# Encoder.net
KiCad netlist of a schematic drawn in Altium Designer
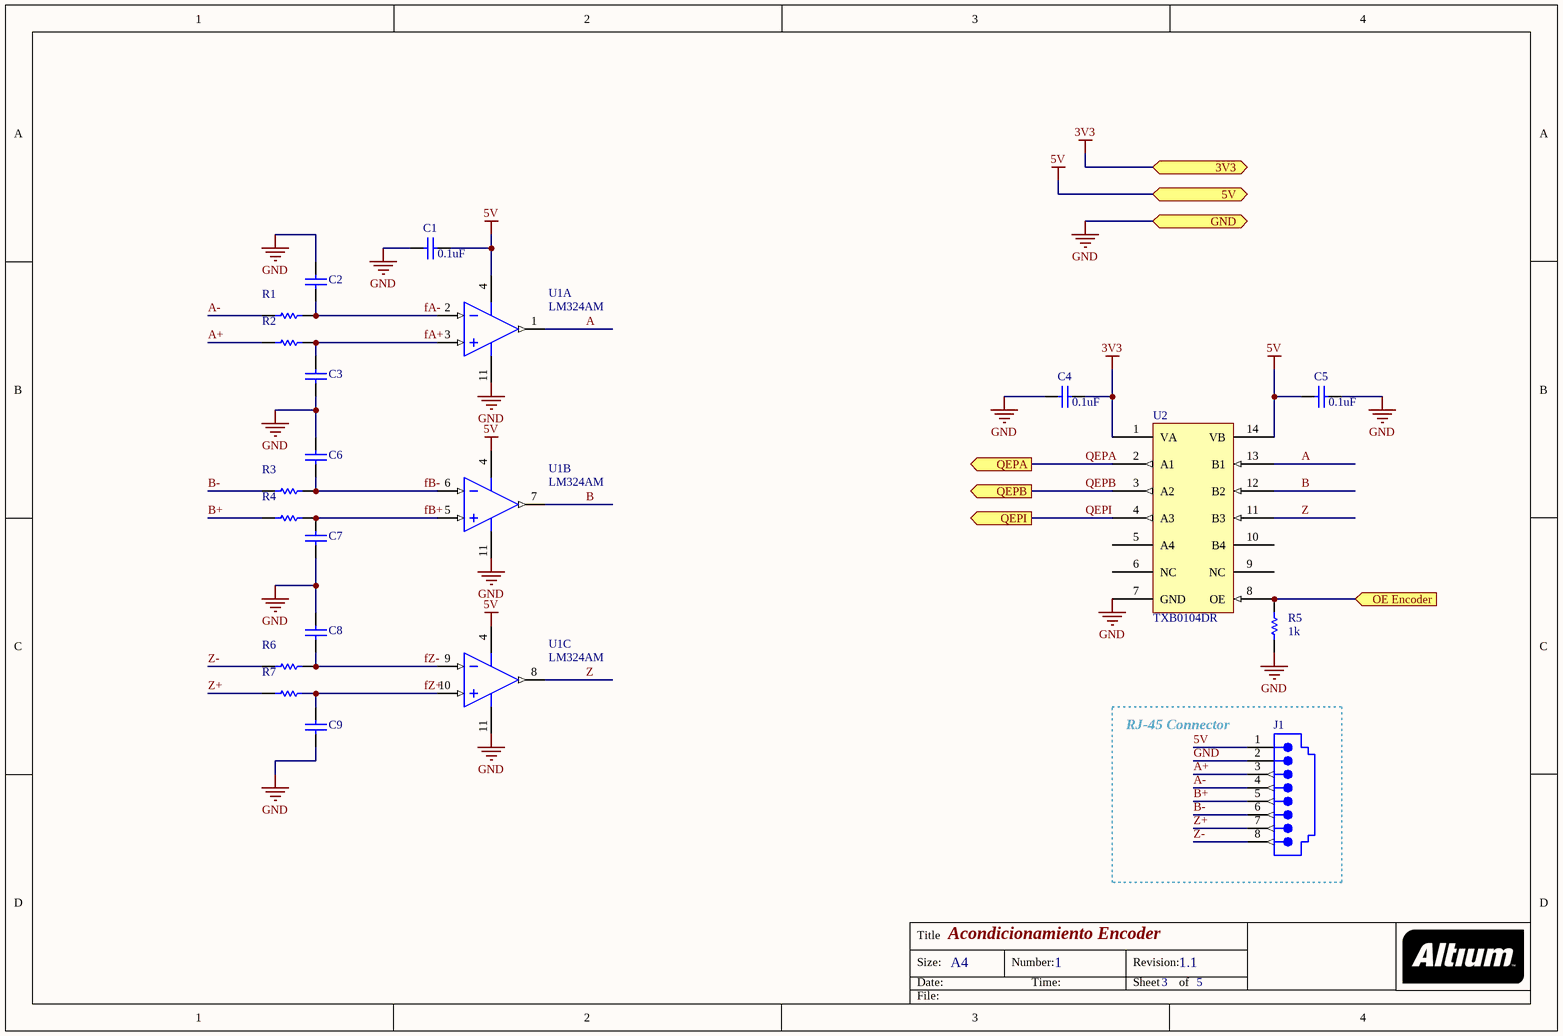
[diagram p0: Encoder.SchDoc]

(export (version "E")
  (design (tool "Eeschema 10.0.6"))
  (components
    (comp (ref "C1")
      (value "0.1uF")
      (footprint "C 1206")
      (description "Capacitor")
      (fields (field (name "Comment") "C0.1u") (field (name ".CREATOR") "SR"))
      (libsource (lib "CDR_SCH") (part "C"))
    )
    (comp (ref "C2")
      (value "C?")
      (footprint "C 1206")
      (description "Capacitor")
      (fields (field (name ".CREATOR") "SR"))
      (libsource (lib "CDR_SCH") (part "C"))
    )
    (comp (ref "C3")
      (value "C?")
      (footprint "C 1206")
      (description "Capacitor")
      (fields (field (name ".CREATOR") "SR"))
      (libsource (lib "CDR_SCH") (part "C"))
    )
    (comp (ref "C4")
      (value "0.1uF")
      (footprint "C 1206")
      (description "Capacitor")
      (fields (field (name "Comment") "C0.1u") (field (name ".CREATOR") "SR"))
      (libsource (lib "CDR_SCH") (part "C"))
    )
    (comp (ref "C5")
      (value "0.1uF")
      (footprint "C 1206")
      (description "Capacitor")
      (fields (field (name "Comment") "C0.1u") (field (name ".CREATOR") "SR"))
      (libsource (lib "CDR_SCH") (part "C"))
    )
    (comp (ref "C6")
      (value "C?")
      (footprint "C 1206")
      (description "Capacitor")
      (fields (field (name ".CREATOR") "SR"))
      (libsource (lib "CDR_SCH") (part "C"))
    )
    (comp (ref "C7")
      (value "C?")
      (footprint "C 1206")
      (description "Capacitor")
      (fields (field (name ".CREATOR") "SR"))
      (libsource (lib "CDR_SCH") (part "C"))
    )
    (comp (ref "C8")
      (value "C?")
      (footprint "C 1206")
      (description "Capacitor")
      (fields (field (name ".CREATOR") "SR"))
      (libsource (lib "CDR_SCH") (part "C"))
    )
    (comp (ref "C9")
      (value "C?")
      (footprint "C 1206")
      (description "Capacitor")
      (fields (field (name ".CREATOR") "SR"))
      (libsource (lib "CDR_SCH") (part "C"))
    )
    (comp (ref "J1")
      (value "RJ-45 connector")
      (footprint "15-43-6588")
      (description "RJ-45 connector, 8-pins, ethernet")
      (fields (field (name "PUBLISHER") "Altium Limited"))
      (libsource (lib "Molex Modular Jack Right Angle") (part "15-43-6588"))
    )
    (comp (ref "R1")
      (value "R?")
      (footprint "R 1206")
      (description "Resistencia")
      (fields (field (name ".CREATOR") "SR"))
      (libsource (lib "CDR_SCH") (part "R"))
    )
    (comp (ref "R2")
      (value "R?")
      (footprint "R 1206")
      (description "Resistencia")
      (fields (field (name ".CREATOR") "SR"))
      (libsource (lib "CDR_SCH") (part "R"))
    )
    (comp (ref "R3")
      (value "R?")
      (footprint "R 1206")
      (description "Resistencia")
      (fields (field (name ".CREATOR") "SR"))
      (libsource (lib "CDR_SCH") (part "R"))
    )
    (comp (ref "R4")
      (value "R?")
      (footprint "R 1206")
      (description "Resistencia")
      (fields (field (name ".CREATOR") "SR"))
      (libsource (lib "CDR_SCH") (part "R"))
    )
    (comp (ref "R5")
      (value "1k")
      (footprint "R 1206")
      (description "Resistencia")
      (fields (field (name "Comment") "R1k") (field (name ".CREATOR") "SR"))
      (libsource (lib "CDR_SCH") (part "R"))
    )
    (comp (ref "R6")
      (value "R?")
      (footprint "R 1206")
      (description "Resistencia")
      (fields (field (name ".CREATOR") "SR"))
      (libsource (lib "CDR_SCH") (part "R"))
    )
    (comp (ref "R7")
      (value "R?")
      (footprint "R 1206")
      (description "Resistencia")
      (fields (field (name ".CREATOR") "SR"))
      (libsource (lib "CDR_SCH") (part "R"))
    )
    (comp (ref "U1")
      (value "LM324AM")
      (footprint "M14A_N")
      (description "Low Power Quad Operational Amplifier, 14-pin Narrow SOIC")
      (fields (field (name "MANUFACTURER") "National Semiconductor"))
      (libsource (lib "National Semiconductor Amplifier") (part "LM324AM"))
    )
    (comp (ref "U2")
      (value "TXB0104DR")
      (footprint "SOIC-14")
      (description "IC VOLT-LEVEL TRANSLATOR 14-SOIC")
      (fields (field (name "MANUFACTURER") "Texas Instruments"))
      (libsource (lib "CDR_SCH") (part "TXB0104DR"))
    )
  )
  (nets
    (net (code "1") (name "/A") (class "Default")
      (node (ref "U1") (pin "1") (pinfunction "OUT1_1") (pintype "output"))
      (node (ref "U2") (pin "13") (pinfunction "B1_13") (pintype "input"))
    )
    (net (code "2") (name "/A+") (class "Default")
      (node (ref "J1") (pin "3") (pinfunction "3_3") (pintype "output"))
      (node (ref "R2") (pin "2") (pinfunction "2_2") (pintype "passive"))
    )
    (net (code "3") (name "/A-") (class "Default")
      (node (ref "J1") (pin "4") (pinfunction "4_4") (pintype "output"))
      (node (ref "R1") (pin "2") (pinfunction "2_2") (pintype "passive"))
    )
    (net (code "4") (name "/B") (class "Default")
      (node (ref "U1") (pin "7") (pinfunction "OUT2_7") (pintype "output"))
      (node (ref "U2") (pin "12") (pinfunction "B2_12") (pintype "input"))
    )
    (net (code "5") (name "/B+") (class "Default")
      (node (ref "J1") (pin "5") (pinfunction "5_5") (pintype "output"))
      (node (ref "R4") (pin "2") (pinfunction "2_2") (pintype "passive"))
    )
    (net (code "6") (name "/B-") (class "Default")
      (node (ref "J1") (pin "6") (pinfunction "6_6") (pintype "output"))
      (node (ref "R3") (pin "2") (pinfunction "2_2") (pintype "passive"))
    )
    (net (code "7") (name "/OE Encoder") (class "Default")
      (node (ref "R5") (pin "2") (pinfunction "2_2") (pintype "passive"))
      (node (ref "U2") (pin "8") (pinfunction "OE_8") (pintype "input"))
    )
    (net (code "8") (name "/QEPA") (class "Default")
      (node (ref "U2") (pin "2") (pinfunction "A1_2") (pintype "output"))
    )
    (net (code "9") (name "/QEPB") (class "Default")
      (node (ref "U2") (pin "3") (pinfunction "A2_3") (pintype "output"))
    )
    (net (code "10") (name "/QEPI") (class "Default")
      (node (ref "U2") (pin "4") (pinfunction "A3_4") (pintype "output"))
    )
    (net (code "11") (name "/Z") (class "Default")
      (node (ref "U1") (pin "8") (pinfunction "OUT3_8") (pintype "output"))
      (node (ref "U2") (pin "11") (pinfunction "B3_11") (pintype "input"))
    )
    (net (code "12") (name "/Z+") (class "Default")
      (node (ref "J1") (pin "7") (pinfunction "7_7") (pintype "output"))
      (node (ref "R7") (pin "2") (pinfunction "2_2") (pintype "passive"))
    )
    (net (code "13") (name "/Z-") (class "Default")
      (node (ref "J1") (pin "8") (pinfunction "8_8") (pintype "output"))
      (node (ref "R6") (pin "2") (pinfunction "2_2") (pintype "passive"))
    )
    (net (code "14") (name "/fA+") (class "Default")
      (node (ref "C3") (pin "2") (pinfunction "2_2") (pintype "passive"))
      (node (ref "R2") (pin "1") (pinfunction "1_1") (pintype "passive"))
      (node (ref "U1") (pin "3") (pinfunction "IN1+_3") (pintype "input"))
    )
    (net (code "15") (name "/fA-") (class "Default")
      (node (ref "C2") (pin "1") (pinfunction "1_1") (pintype "passive"))
      (node (ref "R1") (pin "1") (pinfunction "1_1") (pintype "passive"))
      (node (ref "U1") (pin "2") (pinfunction "IN1-_2") (pintype "input"))
    )
    (net (code "16") (name "/fB+") (class "Default")
      (node (ref "C7") (pin "2") (pinfunction "2_2") (pintype "passive"))
      (node (ref "R4") (pin "1") (pinfunction "1_1") (pintype "passive"))
      (node (ref "U1") (pin "5") (pinfunction "IN2+_5") (pintype "input"))
    )
    (net (code "17") (name "/fB-") (class "Default")
      (node (ref "C6") (pin "1") (pinfunction "1_1") (pintype "passive"))
      (node (ref "R3") (pin "1") (pinfunction "1_1") (pintype "passive"))
      (node (ref "U1") (pin "6") (pinfunction "IN2-_6") (pintype "input"))
    )
    (net (code "18") (name "/fZ+") (class "Default")
      (node (ref "C9") (pin "2") (pinfunction "2_2") (pintype "passive"))
      (node (ref "R7") (pin "1") (pinfunction "1_1") (pintype "passive"))
      (node (ref "U1") (pin "10") (pinfunction "IN3+_10") (pintype "input"))
    )
    (net (code "19") (name "/fZ-") (class "Default")
      (node (ref "C8") (pin "1") (pinfunction "1_1") (pintype "passive"))
      (node (ref "R6") (pin "1") (pinfunction "1_1") (pintype "passive"))
      (node (ref "U1") (pin "9") (pinfunction "IN3-_9") (pintype "input"))
    )
    (net (code "20") (name "3V3") (class "Default")
      (node (ref "C4") (pin "2") (pinfunction "2_2") (pintype "passive"))
      (node (ref "U2") (pin "1") (pinfunction "VA_1") (pintype "power_in"))
    )
    (net (code "21") (name "5V") (class "Default")
      (node (ref "C1") (pin "2") (pinfunction "2_2") (pintype "passive"))
      (node (ref "C5") (pin "1") (pinfunction "1_1") (pintype "passive"))
      (node (ref "J1") (pin "1") (pinfunction "1_1") (pintype "power_in"))
      (node (ref "U1") (pin "4") (pinfunction "V+_4") (pintype "power_in"))
      (node (ref "U2") (pin "14") (pinfunction "VB_14") (pintype "power_in"))
    )
    (net (code "22") (name "GND") (class "Default")
      (node (ref "C1") (pin "1") (pinfunction "1_1") (pintype "passive"))
      (node (ref "C2") (pin "2") (pinfunction "2_2") (pintype "passive"))
      (node (ref "C3") (pin "1") (pinfunction "1_1") (pintype "passive"))
      (node (ref "C4") (pin "1") (pinfunction "1_1") (pintype "passive"))
      (node (ref "C5") (pin "2") (pinfunction "2_2") (pintype "passive"))
      (node (ref "C6") (pin "2") (pinfunction "2_2") (pintype "passive"))
      (node (ref "C7") (pin "1") (pinfunction "1_1") (pintype "passive"))
      (node (ref "C8") (pin "2") (pinfunction "2_2") (pintype "passive"))
      (node (ref "C9") (pin "1") (pinfunction "1_1") (pintype "passive"))
      (node (ref "J1") (pin "2") (pinfunction "2_2") (pintype "power_in"))
      (node (ref "R5") (pin "1") (pinfunction "1_1") (pintype "passive"))
      (node (ref "U1") (pin "11") (pinfunction "GND_11") (pintype "power_in"))
      (node (ref "U2") (pin "7") (pinfunction "GND_7") (pintype "power_in"))
    )
    (net (code "23") (name "unconnected-(U2-A4-Pad5)") (class "Default")
      (node (ref "U2") (pin "5") (pinfunction "A4_5") (pintype "tri_state"))
    )
    (net (code "24") (name "unconnected-(U2-B4-Pad10)") (class "Default")
      (node (ref "U2") (pin "10") (pinfunction "B4_10") (pintype "tri_state"))
    )
    (net (code "25") (name "unconnected-(U2-NC-Pad6)") (class "Default")
      (node (ref "U2") (pin "6") (pinfunction "NC_6") (pintype "tri_state"))
    )
    (net (code "26") (name "unconnected-(U2-NC-Pad9)") (class "Default")
      (node (ref "U2") (pin "9") (pinfunction "NC_9") (pintype "tri_state"))
    )
  )
)
